# Display.net
KiCad netlist of a schematic drawn in Altium Designer
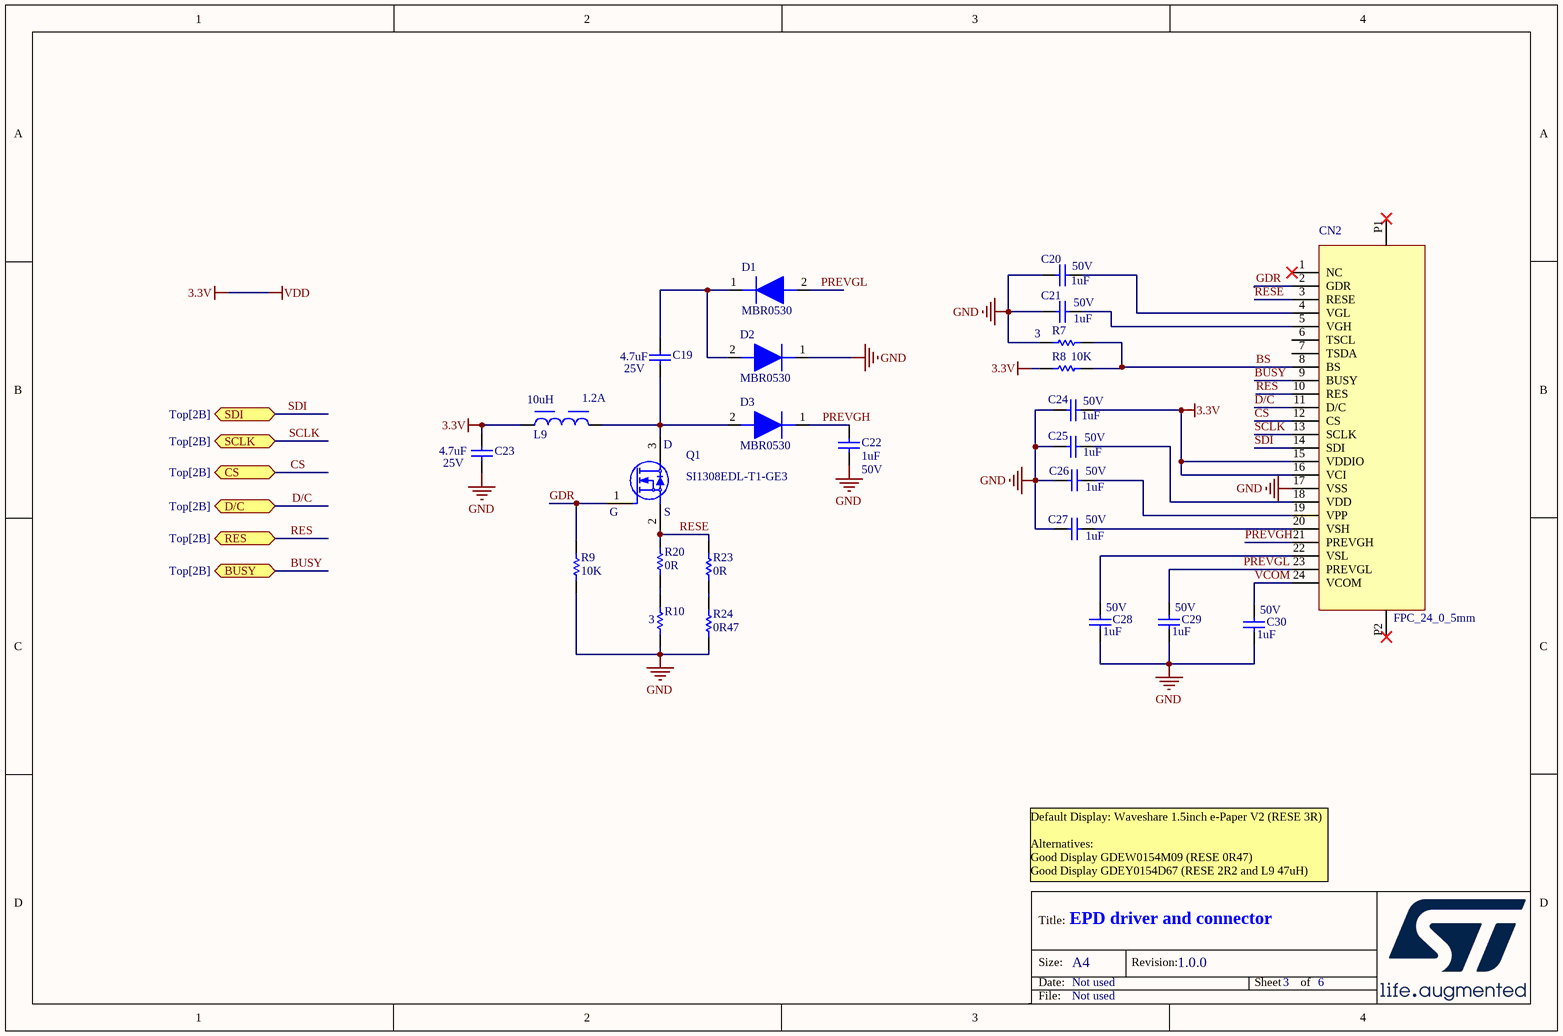
[diagram p0: Display.SchDoc]

(export (version "E")
  (design (tool "Eeschema 10.0.6"))
  (components
    (comp (ref "C19")
      (value "4.7uF")
      (footprint "C0603")
      (description "CAP CER 4.7UF 25V X6S 0603")
      (fields
        (field (name "MANUFACTURER") "Murata")
        (field (name "MANUFACTURER PART NUMBER") "GRM188C81E475KE11D")
        (field (name "VOLTAGE") "25V")
      )
      (libsource (lib "MCD_PARTS_database") (part "Capacitor"))
    )
    (comp (ref "C20")
      (value "1uF")
      (footprint "C0603_H0P8")
      (description "Multilayer Ceramic Capacitor, 1 uF, 50 V, ± 10%, X5R, 0603 [1608 Metric]")
      (fields
        (field (name "MANUFACTURER") "Murata")
        (field (name "MANUFACTURER PART NUMBER") "GRT188R61H105KE13D")
        (field (name "VOLTAGE RATING") "50V")
      )
      (libsource (lib "MCD_PARTS_database") (part "Capacitor"))
    )
    (comp (ref "C21")
      (value "1uF")
      (footprint "C0603_H0P8")
      (description "Multilayer Ceramic Capacitor, 1 uF, 50 V, ± 10%, X5R, 0603 [1608 Metric]")
      (fields
        (field (name "MANUFACTURER") "Murata")
        (field (name "MANUFACTURER PART NUMBER") "GRT188R61H105KE13D")
        (field (name "VOLTAGE RATING") "50V")
      )
      (libsource (lib "MCD_PARTS_database") (part "Capacitor"))
    )
    (comp (ref "C22")
      (value "1uF")
      (footprint "C0603_H0P8")
      (description "Multilayer Ceramic Capacitor, 1 uF, 50 V, ± 10%, X5R, 0603 [1608 Metric]")
      (fields
        (field (name "MANUFACTURER") "Murata")
        (field (name "MANUFACTURER PART NUMBER") "GRT188R61H105KE13D")
        (field (name "VOLTAGE RATING") "50V")
      )
      (libsource (lib "MCD_PARTS_database") (part "Capacitor"))
    )
    (comp (ref "C23")
      (value "4.7uF")
      (footprint "C0603")
      (description "CAP CER 4.7UF 25V X6S 0603")
      (fields
        (field (name "MANUFACTURER") "Murata")
        (field (name "MANUFACTURER PART NUMBER") "GRM188C81E475KE11D")
        (field (name "VOLTAGE") "25V")
      )
      (libsource (lib "MCD_PARTS_database") (part "Capacitor"))
    )
    (comp (ref "C24")
      (value "1uF")
      (footprint "C0603_H0P8")
      (description "Multilayer Ceramic Capacitor, 1 uF, 50 V, ± 10%, X5R, 0603 [1608 Metric]")
      (fields
        (field (name "MANUFACTURER") "Murata")
        (field (name "MANUFACTURER PART NUMBER") "GRT188R61H105KE13D")
        (field (name "VOLTAGE RATING") "50V")
      )
      (libsource (lib "MCD_PARTS_database") (part "Capacitor"))
    )
    (comp (ref "C25")
      (value "1uF")
      (footprint "C0603_H0P8")
      (description "Multilayer Ceramic Capacitor, 1 uF, 50 V, ± 10%, X5R, 0603 [1608 Metric]")
      (fields
        (field (name "MANUFACTURER") "Murata")
        (field (name "MANUFACTURER PART NUMBER") "GRT188R61H105KE13D")
        (field (name "VOLTAGE RATING") "50V")
      )
      (libsource (lib "MCD_PARTS_database") (part "Capacitor"))
    )
    (comp (ref "C26")
      (value "1uF")
      (footprint "C0603_H0P8")
      (description "Multilayer Ceramic Capacitor, 1 uF, 50 V, ± 10%, X5R, 0603 [1608 Metric]")
      (fields
        (field (name "MANUFACTURER") "Murata")
        (field (name "MANUFACTURER PART NUMBER") "GRT188R61H105KE13D")
        (field (name "VOLTAGE RATING") "50V")
      )
      (libsource (lib "MCD_PARTS_database") (part "Capacitor"))
    )
    (comp (ref "C27")
      (value "1uF")
      (footprint "C0603_H0P8")
      (description "Multilayer Ceramic Capacitor, 1 uF, 50 V, ± 10%, X5R, 0603 [1608 Metric]")
      (fields
        (field (name "MANUFACTURER") "Murata")
        (field (name "MANUFACTURER PART NUMBER") "GRT188R61H105KE13D")
        (field (name "VOLTAGE RATING") "50V")
      )
      (libsource (lib "MCD_PARTS_database") (part "Capacitor"))
    )
    (comp (ref "C28")
      (value "1uF")
      (footprint "C0603_H0P8")
      (description "Multilayer Ceramic Capacitor, 1 uF, 50 V, ± 10%, X5R, 0603 [1608 Metric]")
      (fields
        (field (name "MANUFACTURER") "Murata")
        (field (name "MANUFACTURER PART NUMBER") "GRT188R61H105KE13D")
        (field (name "VOLTAGE RATING") "50V")
      )
      (libsource (lib "MCD_PARTS_database") (part "Capacitor"))
    )
    (comp (ref "C29")
      (value "1uF")
      (footprint "C0603_H0P8")
      (description "Multilayer Ceramic Capacitor, 1 uF, 50 V, ± 10%, X5R, 0603 [1608 Metric]")
      (fields
        (field (name "MANUFACTURER") "Murata")
        (field (name "MANUFACTURER PART NUMBER") "GRT188R61H105KE13D")
        (field (name "VOLTAGE RATING") "50V")
      )
      (libsource (lib "MCD_PARTS_database") (part "Capacitor"))
    )
    (comp (ref "C30")
      (value "1uF")
      (footprint "C0603_H0P8")
      (description "Multilayer Ceramic Capacitor, 1 uF, 50 V, ± 10%, X5R, 0603 [1608 Metric]")
      (fields
        (field (name "MANUFACTURER") "Murata")
        (field (name "MANUFACTURER PART NUMBER") "GRT188R61H105KE13D")
        (field (name "VOLTAGE RATING") "50V")
      )
      (libsource (lib "MCD_PARTS_database") (part "Capacitor"))
    )
    (comp (ref "CN2")
      (value "FPC_24_0_5mm")
      (footprint "CON_5034802400_MOL")
      (description "Conn, Ffc/fpc, R/a, 24Pos, 1Row, 0.5Mm Rohs Compliant: Yes")
      (fields (field (name "MANUFACTURER") "Molex") (field (name "MANUFACTURER PART NUMBER") "503480-2400"))
      (libsource (lib "missing_parts") (part "FPC_24_0_5mm"))
    )
    (comp (ref "D1")
      (value "MBR0530")
      (footprint "SOD3716X135N")
      (description "Diode, Schottky Barrier, Vr 30V, If 0.5A, Pkg SOD-123, Vf 0.43V, Tj +125degc, Cs 5.5A")
      (fields
        (field (name "MANUFACTURER") "ON Semiconductor / Fairchild")
        (field (name "MANUFACTURER PART NUMBER") "MBR0530T1G")
      )
      (libsource (lib "missing_parts") (part "MBR0530"))
    )
    (comp (ref "D2")
      (value "MBR0530")
      (footprint "SOD3716X135N")
      (description "Diode, Schottky Barrier, Vr 30V, If 0.5A, Pkg SOD-123, Vf 0.43V, Tj +125degc, Cs 5.5A")
      (fields
        (field (name "MANUFACTURER") "ON Semiconductor / Fairchild")
        (field (name "MANUFACTURER PART NUMBER") "MBR0530T1G")
      )
      (libsource (lib "missing_parts") (part "MBR0530"))
    )
    (comp (ref "D3")
      (value "MBR0530")
      (footprint "SOD3716X135N")
      (description "Diode, Schottky Barrier, Vr 30V, If 0.5A, Pkg SOD-123, Vf 0.43V, Tj +125degc, Cs 5.5A")
      (fields
        (field (name "MANUFACTURER") "ON Semiconductor / Fairchild")
        (field (name "MANUFACTURER PART NUMBER") "MBR0530T1G")
      )
      (libsource (lib "missing_parts") (part "MBR0530"))
    )
    (comp (ref "L9")
      (value "10uH, 1.2A")
      (footprint "WE-LQS_4018")
      (description "WE-LQS SMT Power Inductor, size 4018, 10uH, 1.2A, 0.15Ohm")
      (fields
        (field (name "MANUFACTURER PART NUMBER") "74404042100")
        (field (name "MANUFACTURER") "Wurth Elektronik")
        (field (name "INDUCTANCE") "10uH")
        (field (name "RATED CURRENT") "1.2A")
      )
      (libsource (lib "missing_parts") (part "74404042100"))
    )
    (comp (ref "Q1")
      (value "SI1308EDL-T1-GE3")
      (footprint "MOS_SOT323-3L")
      (description "Transistor, MOSFET, N-CH, 30V, 1.4A, SOT-323")
      (fields (field (name "INTERNAL_PART_NUMBER") "MCD-02504") (field (name "MANUFACTURER") "VISHAY"))
      (libsource (lib "missing_parts") (part "SI1308EDL"))
    )
    (comp (ref "R7")
      (value "3")
      (footprint "R0402")
      (description "Res Thick Film 0402 3 Ohm 1% 1/16W ±200ppm/°C Molded SMD Paper T/R")
      (fields
        (field (name "MANUFACTURER") "Yageo")
        (field (name "MANUFACTURER PART NUMBER") "RC0402FR-073RL")
      )
      (libsource (lib "MCD_PARTS_database") (part "Resistor"))
    )
    (comp (ref "R8")
      (value "10K")
      (footprint "R0402")
      (description "Resistor, 10K, 0402, +/-0.1%, 1/16W, +/-25ppm/°C")
      (fields (field (name "INTERNAL_PART_NUMBER") "MCD-02551") (field (name "MANUFACTURER") "YAGEO"))
      (libsource (lib "MCD_PARTS_database") (part "Resistor"))
    )
    (comp (ref "R9")
      (value "10K")
      (footprint "R0402")
      (description "Resistor, 10K, 0402, +/-0.1%, 1/16W, +/-25ppm/°C")
      (fields (field (name "INTERNAL_PART_NUMBER") "MCD-02551") (field (name "MANUFACTURER") "YAGEO"))
      (libsource (lib "MCD_PARTS_database") (part "Resistor"))
    )
    (comp (ref "R10")
      (value "3")
      (footprint "R0402")
      (description "Res Thick Film 0402 3 Ohm 1% 1/16W ±200ppm/°C Molded SMD Paper T/R")
      (fields
        (field (name "MANUFACTURER") "Yageo")
        (field (name "MANUFACTURER PART NUMBER") "RC0402FR-073RL")
      )
      (libsource (lib "MCD_PARTS_database") (part "Resistor"))
    )
    (comp (ref "R20")
      (value "0R")
      (footprint "R0402")
      (description "Resistor, 0R, 0402, +/-5%, 1/16W")
      (fields (field (name "INTERNAL_PART_NUMBER") "MCD-00052") (field (name "MANUFACTURER") "YAGEO"))
      (libsource (lib "MCD_PARTS_database") (part "Resistor"))
    )
    (comp (ref "R23")
      (value "0R")
      (footprint "R0402")
      (description "Resistor, 0R, 0402, +/-5%, 1/16W")
      (fields (field (name "INTERNAL_PART_NUMBER") "MCD-00052") (field (name "MANUFACTURER") "YAGEO"))
      (libsource (lib "MCD_PARTS_database") (part "Resistor"))
    )
    (comp (ref "R24")
      (value "0R47")
      (footprint "R0402")
      (description "Resistor, 0R47, 0402, +/-1%, 1/16W")
      (fields (field (name "INTERNAL_PART_NUMBER") "MCD-02517") (field (name "MANUFACTURER") "YAGEO"))
      (libsource (lib "MCD_PARTS_database") (part "Resistor"))
    )
  )
  (nets
    (net (code "1") (name "/BS") (class "Default")
      (node (ref "CN2") (pin "8") (pinfunction "BS_8") (pintype "passive"))
      (node (ref "R7") (pin "1") (pinfunction "1_1") (pintype "passive"))
      (node (ref "R8") (pin "2") (pinfunction "2_2") (pintype "passive"))
    )
    (net (code "2") (name "/BUSY") (class "Default")
      (node (ref "CN2") (pin "9") (pinfunction "BUSY_9") (pintype "passive"))
    )
    (net (code "3") (name "/CS") (class "Default")
      (node (ref "CN2") (pin "12") (pinfunction "CS_12") (pintype "passive"))
    )
    (net (code "4") (name "/D{slash}C") (class "Default")
      (node (ref "CN2") (pin "11") (pinfunction "D/C_11") (pintype "passive"))
    )
    (net (code "5") (name "/GDR") (class "Default")
      (node (ref "CN2") (pin "2") (pinfunction "GDR_2") (pintype "passive"))
      (node (ref "Q1") (pin "1") (pinfunction "G_1") (pintype "passive"))
      (node (ref "R9") (pin "2") (pinfunction "2_2") (pintype "passive"))
    )
    (net (code "6") (name "/PREVGH") (class "Default")
      (node (ref "C22") (pin "2") (pinfunction "2_2") (pintype "passive"))
      (node (ref "CN2") (pin "21") (pinfunction "PREVGH_21") (pintype "passive"))
      (node (ref "D3") (pin "1") (pinfunction "1_1") (pintype "passive"))
    )
    (net (code "7") (name "/PREVGL") (class "Default")
      (node (ref "C29") (pin "2") (pinfunction "2_2") (pintype "passive"))
      (node (ref "CN2") (pin "23") (pinfunction "PREVGL_23") (pintype "passive"))
      (node (ref "D1") (pin "2") (pinfunction "2_2") (pintype "passive"))
    )
    (net (code "8") (name "/RES") (class "Default")
      (node (ref "CN2") (pin "10") (pinfunction "RES_10") (pintype "passive"))
    )
    (net (code "9") (name "/RESE") (class "Default")
      (node (ref "CN2") (pin "3") (pinfunction "RESE_3") (pintype "passive"))
      (node (ref "Q1") (pin "2") (pinfunction "S_2") (pintype "passive"))
      (node (ref "R20") (pin "2") (pinfunction "2_2") (pintype "passive"))
      (node (ref "R23") (pin "2") (pinfunction "2_2") (pintype "passive"))
    )
    (net (code "10") (name "/SCLK") (class "Default")
      (node (ref "CN2") (pin "13") (pinfunction "SCLK_13") (pintype "passive"))
    )
    (net (code "11") (name "/SDI") (class "Default")
      (node (ref "CN2") (pin "14") (pinfunction "SDI_14") (pintype "passive"))
    )
    (net (code "12") (name "/VCOM") (class "Default")
      (node (ref "C30") (pin "2") (pinfunction "2_2") (pintype "passive"))
      (node (ref "CN2") (pin "24") (pinfunction "VCOM_24") (pintype "passive"))
    )
    (net (code "13") (name "3.3V") (class "Default")
      (node (ref "C23") (pin "2") (pinfunction "2_2") (pintype "passive"))
      (node (ref "C24") (pin "2") (pinfunction "2_2") (pintype "passive"))
      (node (ref "CN2") (pin "15") (pinfunction "VDDIO_15") (pintype "passive"))
      (node (ref "CN2") (pin "16") (pinfunction "VCI_16") (pintype "passive"))
      (node (ref "L9") (pin "1") (pinfunction "1_1") (pintype "passive"))
      (node (ref "R8") (pin "1") (pinfunction "1_1") (pintype "passive"))
    )
    (net (code "14") (name "GND") (class "Default")
      (node (ref "C20") (pin "1") (pinfunction "1_1") (pintype "passive"))
      (node (ref "C21") (pin "1") (pinfunction "1_1") (pintype "passive"))
      (node (ref "C22") (pin "1") (pinfunction "1_1") (pintype "passive"))
      (node (ref "C23") (pin "1") (pinfunction "1_1") (pintype "passive"))
      (node (ref "C24") (pin "1") (pinfunction "1_1") (pintype "passive"))
      (node (ref "C25") (pin "1") (pinfunction "1_1") (pintype "passive"))
      (node (ref "C26") (pin "1") (pinfunction "1_1") (pintype "passive"))
      (node (ref "C27") (pin "1") (pinfunction "1_1") (pintype "passive"))
      (node (ref "C28") (pin "1") (pinfunction "1_1") (pintype "passive"))
      (node (ref "C29") (pin "1") (pinfunction "1_1") (pintype "passive"))
      (node (ref "C30") (pin "1") (pinfunction "1_1") (pintype "passive"))
      (node (ref "CN2") (pin "17") (pinfunction "VSS_17") (pintype "passive"))
      (node (ref "D2") (pin "1") (pinfunction "1_1") (pintype "passive"))
      (node (ref "R10") (pin "1") (pinfunction "1_1") (pintype "passive"))
      (node (ref "R24") (pin "2") (pinfunction "2_2") (pintype "passive"))
      (node (ref "R7") (pin "2") (pinfunction "2_2") (pintype "passive"))
      (node (ref "R9") (pin "1") (pinfunction "1_1") (pintype "passive"))
    )
    (net (code "15") (name "Net-(C19-Pad2)") (class "Default")
      (node (ref "C19") (pin "2") (pinfunction "2_2") (pintype "passive"))
      (node (ref "D1") (pin "1") (pinfunction "1_1") (pintype "passive"))
      (node (ref "D2") (pin "2") (pinfunction "2_2") (pintype "passive"))
    )
    (net (code "16") (name "Net-(CN2-VDD)") (class "Default")
      (node (ref "C25") (pin "2") (pinfunction "2_2") (pintype "passive"))
      (node (ref "CN2") (pin "18") (pinfunction "VDD_18") (pintype "passive"))
    )
    (net (code "17") (name "Net-(CN2-VGH)") (class "Default")
      (node (ref "C21") (pin "2") (pinfunction "2_2") (pintype "passive"))
      (node (ref "CN2") (pin "5") (pinfunction "VGH_5") (pintype "passive"))
    )
    (net (code "18") (name "Net-(CN2-VGL)") (class "Default")
      (node (ref "C20") (pin "2") (pinfunction "2_2") (pintype "passive"))
      (node (ref "CN2") (pin "4") (pinfunction "VGL_4") (pintype "passive"))
    )
    (net (code "19") (name "Net-(CN2-VPP)") (class "Default")
      (node (ref "C26") (pin "2") (pinfunction "2_2") (pintype "passive"))
      (node (ref "CN2") (pin "19") (pinfunction "VPP_19") (pintype "passive"))
    )
    (net (code "20") (name "Net-(CN2-VSH)") (class "Default")
      (node (ref "C27") (pin "2") (pinfunction "2_2") (pintype "passive"))
      (node (ref "CN2") (pin "20") (pinfunction "VSH_20") (pintype "passive"))
    )
    (net (code "21") (name "Net-(CN2-VSL)") (class "Default")
      (node (ref "C28") (pin "2") (pinfunction "2_2") (pintype "passive"))
      (node (ref "CN2") (pin "22") (pinfunction "VSL_22") (pintype "passive"))
    )
    (net (code "22") (name "Net-(Q1-D)") (class "Default")
      (node (ref "C19") (pin "1") (pinfunction "1_1") (pintype "passive"))
      (node (ref "D3") (pin "2") (pinfunction "2_2") (pintype "passive"))
      (node (ref "L9") (pin "2") (pinfunction "2_2") (pintype "passive"))
      (node (ref "Q1") (pin "3") (pinfunction "D_3") (pintype "passive"))
    )
    (net (code "23") (name "Net-(R10-Pad2)") (class "Default")
      (node (ref "R10") (pin "2") (pinfunction "2_2") (pintype "passive"))
      (node (ref "R20") (pin "1") (pinfunction "1_1") (pintype "passive"))
    )
    (net (code "24") (name "Net-(R23-Pad1)") (class "Default")
      (node (ref "R23") (pin "1") (pinfunction "1_1") (pintype "passive"))
      (node (ref "R24") (pin "1") (pinfunction "1_1") (pintype "passive"))
    )
    (net (code "25") (name "unconnected-(CN2-NC-Pad1)") (class "Default")
      (node (ref "CN2") (pin "1") (pinfunction "NC_1") (pintype "passive+no_connect"))
    )
    (net (code "26") (name "unconnected-(CN2-NC-PadP1)") (class "Default")
      (node (ref "CN2") (pin "P1") (pinfunction "NC_P1") (pintype "passive+no_connect"))
    )
    (net (code "27") (name "unconnected-(CN2-NC-PadP2)") (class "Default")
      (node (ref "CN2") (pin "P2") (pinfunction "NC_P2") (pintype "passive+no_connect"))
    )
    (net (code "28") (name "unconnected-(CN2-TSCL-Pad6)") (class "Default")
      (node (ref "CN2") (pin "6") (pinfunction "TSCL_6") (pintype "passive"))
    )
    (net (code "29") (name "unconnected-(CN2-TSDA-Pad7)") (class "Default")
      (node (ref "CN2") (pin "7") (pinfunction "TSDA_7") (pintype "passive"))
    )
  )
)
